# gameboyzero-split-top.net
KiCad netlist of a schematic drawn in EAGLE
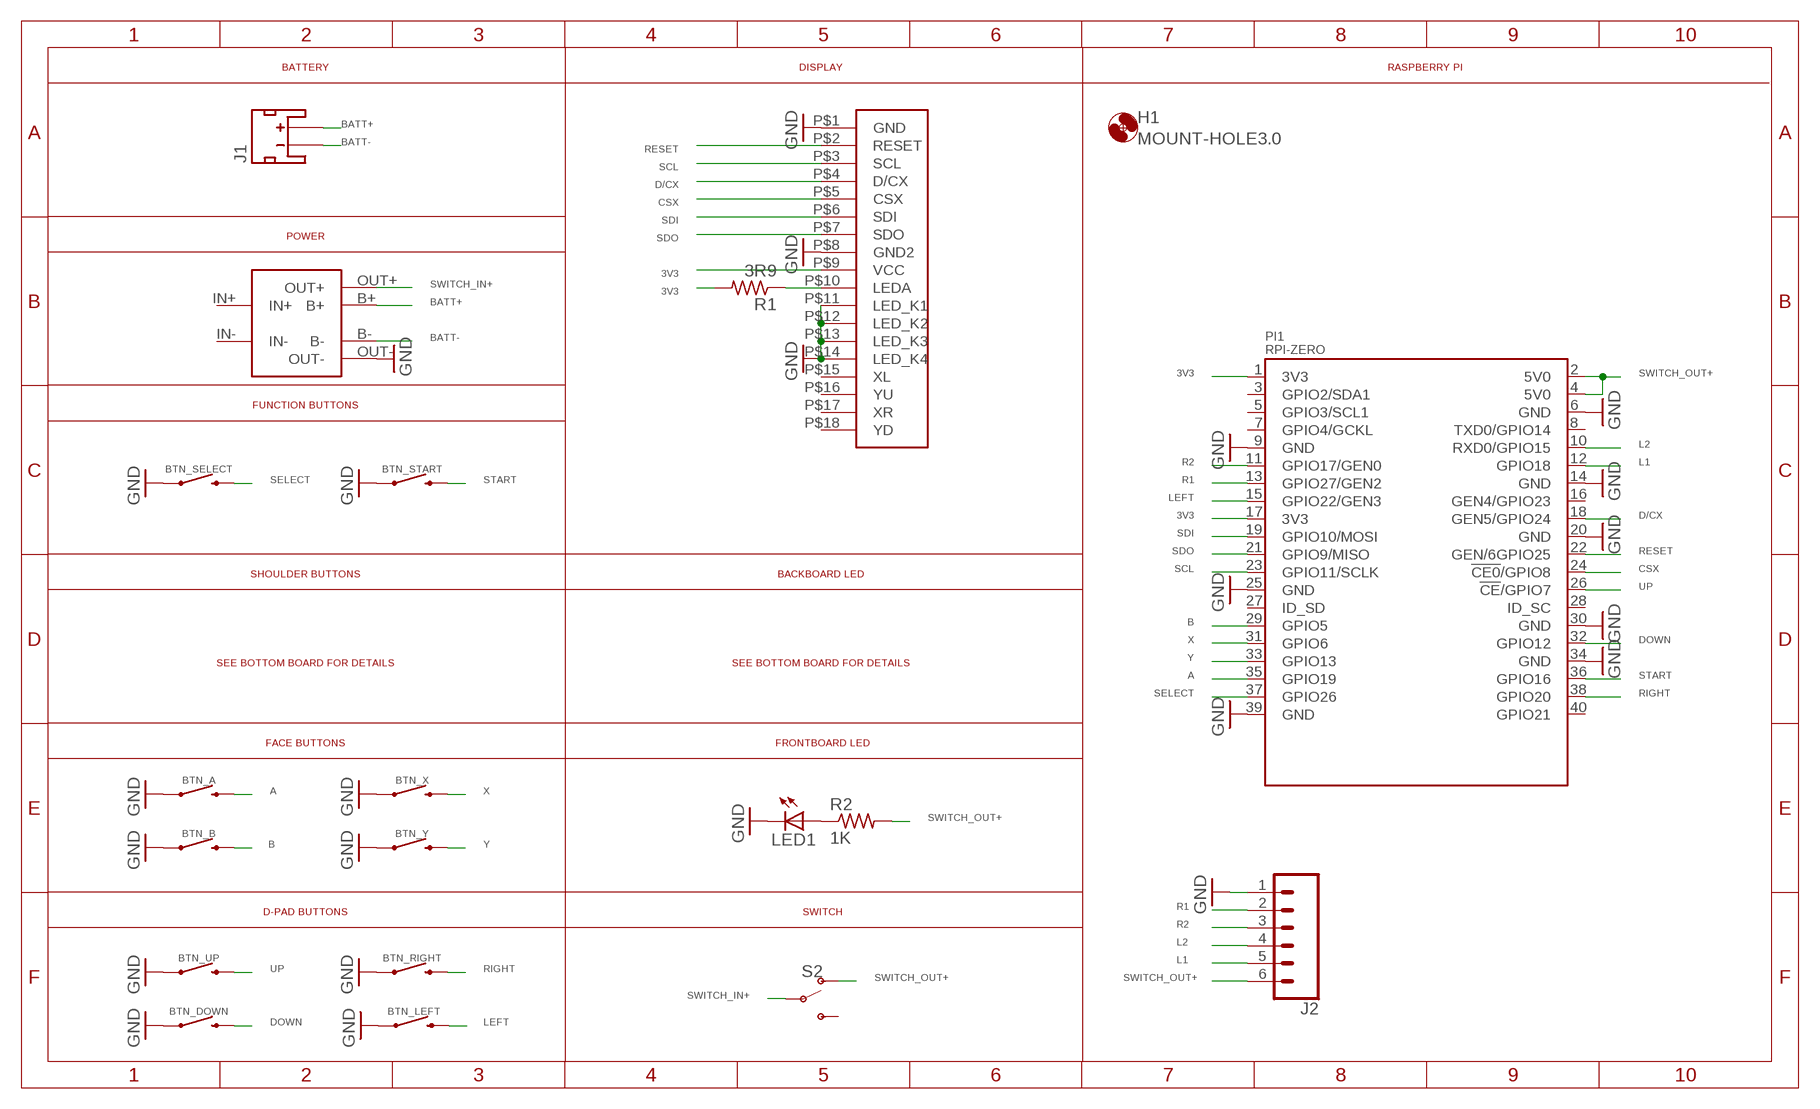
[diagram p0: schematic, sheet 1]

(export (version "E")
  (design (tool "Eeschema 10.0.6"))
  (components
    (comp (ref "BTN_A")
      (value "MOMENTARY-SWITCH-SPST-SMD-12MM")
      (footprint "eagle-import:TACTILE_SWITCH_SMD_12MM")
      (libsource (lib "eagle-import") (part "MOMENTARY-SWITCH-SPST-SMD-12MM"))
    )
    (comp (ref "BTN_B")
      (value "MOMENTARY-SWITCH-SPST-SMD-12MM")
      (footprint "eagle-import:TACTILE_SWITCH_SMD_12MM")
      (libsource (lib "eagle-import") (part "MOMENTARY-SWITCH-SPST-SMD-12MM"))
    )
    (comp (ref "BTN_DOWN")
      (value "MOMENTARY-SWITCH-SPST-SMD-6.2MM-TALL")
      (footprint "eagle-import:TACTILE_SWITCH_SMD_6.2MM_TALL")
      (libsource (lib "eagle-import") (part "MOMENTARY-SWITCH-SPST-SMD-6.2MM-TALL"))
    )
    (comp (ref "BTN_LEFT")
      (value "MOMENTARY-SWITCH-SPST-SMD-6.2MM-TALL")
      (footprint "eagle-import:TACTILE_SWITCH_SMD_6.2MM_TALL")
      (libsource (lib "eagle-import") (part "MOMENTARY-SWITCH-SPST-SMD-6.2MM-TALL"))
    )
    (comp (ref "BTN_RIGHT")
      (value "MOMENTARY-SWITCH-SPST-SMD-6.2MM-TALL")
      (footprint "eagle-import:TACTILE_SWITCH_SMD_6.2MM_TALL")
      (libsource (lib "eagle-import") (part "MOMENTARY-SWITCH-SPST-SMD-6.2MM-TALL"))
    )
    (comp (ref "BTN_SELECT")
      (value "MOMENTARY-SWITCH-SPST-SMD-6.0X3.5MM")
      (footprint "eagle-import:TACTILE_SWITCH_SMD_6.0X3.5MM")
      (libsource (lib "eagle-import") (part "MOMENTARY-SWITCH-SPST-SMD-6.0X3.5MM"))
    )
    (comp (ref "BTN_START")
      (value "MOMENTARY-SWITCH-SPST-SMD-6.0X3.5MM")
      (footprint "eagle-import:TACTILE_SWITCH_SMD_6.0X3.5MM")
      (libsource (lib "eagle-import") (part "MOMENTARY-SWITCH-SPST-SMD-6.0X3.5MM"))
    )
    (comp (ref "BTN_UP")
      (value "MOMENTARY-SWITCH-SPST-SMD-6.2MM-TALL")
      (footprint "eagle-import:TACTILE_SWITCH_SMD_6.2MM_TALL")
      (libsource (lib "eagle-import") (part "MOMENTARY-SWITCH-SPST-SMD-6.2MM-TALL"))
    )
    (comp (ref "BTN_X")
      (value "MOMENTARY-SWITCH-SPST-SMD-12MM")
      (footprint "eagle-import:TACTILE_SWITCH_SMD_12MM")
      (libsource (lib "eagle-import") (part "MOMENTARY-SWITCH-SPST-SMD-12MM"))
    )
    (comp (ref "BTN_Y")
      (value "MOMENTARY-SWITCH-SPST-SMD-12MM")
      (footprint "eagle-import:TACTILE_SWITCH_SMD_12MM")
      (libsource (lib "eagle-import") (part "MOMENTARY-SWITCH-SPST-SMD-12MM"))
    )
    (comp (ref "H1")
      (value "MOUNT-HOLE3.0")
      (footprint "eagle-import:3,0")
      (libsource (lib "eagle-import") (part "MOUNT-HOLE3.0"))
    )
    (comp (ref "J1")
      (value "JST_2MM_MALE")
      (footprint "eagle-import:JST-2-SMD")
      (libsource (lib "eagle-import") (part "JST_2MM_MALE"))
    )
    (comp (ref "J2")
      (value "CONN_06SILK_FEMALE_PTH")
      (footprint "eagle-import:1X06")
      (libsource (lib "eagle-import") (part "CONN_06SILK_FEMALE_PTH"))
    )
    (comp (ref "LED1")
      (value "LEDCHIPLED_0805")
      (footprint "eagle-import:CHIPLED_0805")
      (libsource (lib "eagle-import") (part "LEDCHIPLED_0805"))
    )
    (comp (ref "PI1")
      (value "RPI-ZERO")
      (footprint "eagle-import:RASPBERRYPI_BASTELSTUBE_V13_RASPI_BOARD_B+_FULL")
      (libsource (lib "eagle-import") (part "RPI-ZERO"))
    )
    (comp (ref "POWER1")
      (value "03962A")
      (footprint "eagle-import:03962A")
      (libsource (lib "eagle-import") (part "03962A"))
    )
    (comp (ref "R1")
      (value "3R9")
      (footprint "eagle-import:R0805")
      (libsource (lib "eagle-import") (part "R-US_R0805"))
    )
    (comp (ref "R2")
      (value "1K")
      (footprint "eagle-import:R0805")
      (libsource (lib "eagle-import") (part "R-US_R0805"))
    )
    (comp (ref "S2")
      (value "SWITCH-SPDT-SMD-RIGHT-ANGLE")
      (footprint "eagle-import:SWITCH_SPST_SMD_A")
      (libsource (lib "eagle-import") (part "SWITCH-SPDT-SMD-RIGHT-ANGLE"))
    )
    (comp (ref "SCREEN1")
      (value "GAMEBOYZEROHANDHELDDISPLAYS-2.8")
      (footprint "eagle-import:GAMEBOYZEROHANDHELDDISPLAYS-2.8")
      (libsource (lib "eagle-import") (part "GAMEBOYZEROHANDHELDDISPLAYS-2.8"))
    )
  )
  (nets
    (net (code "1") (name "/3V3") (class "Default")
      (node (ref "PI1") (pin "1") (pinfunction "3V3_1") (pintype "power_in"))
      (node (ref "PI1") (pin "17") (pinfunction "3V3_17") (pintype "power_in"))
      (node (ref "R1") (pin "2") (pinfunction "2_2") (pintype "passive"))
      (node (ref "SCREEN1") (pin "P$9") (pinfunction "VCC_P$9") (pintype "bidirectional"))
    )
    (net (code "2") (name "/A") (class "Default")
      (node (ref "BTN_A") (pin "3") (pinfunction "2_3") (pintype "passive"))
      (node (ref "PI1") (pin "35") (pinfunction "GPIO19_35") (pintype "bidirectional"))
    )
    (net (code "3") (name "/B") (class "Default")
      (node (ref "BTN_B") (pin "3") (pinfunction "2_3") (pintype "passive"))
      (node (ref "PI1") (pin "29") (pinfunction "GPIO5_29") (pintype "bidirectional"))
    )
    (net (code "4") (name "/BATT+") (class "Default")
      (node (ref "J1") (pin "2") (pinfunction "+_2") (pintype "bidirectional"))
      (node (ref "POWER1") (pin "B+") (pinfunction "B+_B+") (pintype "bidirectional"))
    )
    (net (code "5") (name "/BATT-") (class "Default")
      (node (ref "J1") (pin "1") (pinfunction "-_1") (pintype "bidirectional"))
      (node (ref "POWER1") (pin "B-") (pinfunction "B-_B-") (pintype "bidirectional"))
    )
    (net (code "6") (name "/CSX") (class "Default")
      (node (ref "PI1") (pin "24") (pinfunction "~{CE0}/GPIO8_24") (pintype "bidirectional"))
      (node (ref "SCREEN1") (pin "P$5") (pinfunction "CSX_P$5") (pintype "bidirectional"))
    )
    (net (code "7") (name "/DOWN") (class "Default")
      (node (ref "BTN_DOWN") (pin "B2") (pinfunction "2_B2") (pintype "passive"))
      (node (ref "PI1") (pin "32") (pinfunction "GPIO12_32") (pintype "bidirectional"))
    )
    (net (code "8") (name "/D{slash}CX") (class "Default")
      (node (ref "PI1") (pin "18") (pinfunction "GEN5/GPIO24_18") (pintype "bidirectional"))
      (node (ref "SCREEN1") (pin "P$4") (pinfunction "D/CX_P$4") (pintype "bidirectional"))
    )
    (net (code "9") (name "/L1") (class "Default")
      (node (ref "J2") (pin "5") (pinfunction "5_5") (pintype "passive"))
      (node (ref "PI1") (pin "12") (pinfunction "GPIO18_12") (pintype "bidirectional"))
    )
    (net (code "10") (name "/L2") (class "Default")
      (node (ref "J2") (pin "4") (pinfunction "4_4") (pintype "passive"))
      (node (ref "PI1") (pin "10") (pinfunction "RXD0/GPIO15_10") (pintype "bidirectional"))
    )
    (net (code "11") (name "/LEFT") (class "Default")
      (node (ref "BTN_LEFT") (pin "B2") (pinfunction "2_B2") (pintype "passive"))
      (node (ref "PI1") (pin "15") (pinfunction "GPIO22/GEN3_15") (pintype "bidirectional"))
    )
    (net (code "12") (name "/R1") (class "Default")
      (node (ref "J2") (pin "2") (pinfunction "2_2") (pintype "passive"))
      (node (ref "PI1") (pin "13") (pinfunction "GPIO27/GEN2_13") (pintype "bidirectional"))
    )
    (net (code "13") (name "/R2") (class "Default")
      (node (ref "J2") (pin "3") (pinfunction "3_3") (pintype "passive"))
      (node (ref "PI1") (pin "11") (pinfunction "GPIO17/GEN0_11") (pintype "bidirectional"))
    )
    (net (code "14") (name "/RESET") (class "Default")
      (node (ref "PI1") (pin "22") (pinfunction "GEN/6GPIO25_22") (pintype "bidirectional"))
      (node (ref "SCREEN1") (pin "P$2") (pinfunction "RESET_P$2") (pintype "bidirectional"))
    )
    (net (code "15") (name "/RIGHT") (class "Default")
      (node (ref "BTN_RIGHT") (pin "B2") (pinfunction "2_B2") (pintype "passive"))
      (node (ref "PI1") (pin "38") (pinfunction "GPIO20_38") (pintype "bidirectional"))
    )
    (net (code "16") (name "/SCL") (class "Default")
      (node (ref "PI1") (pin "23") (pinfunction "GPIO11/SCLK_23") (pintype "bidirectional"))
      (node (ref "SCREEN1") (pin "P$3") (pinfunction "SCL_P$3") (pintype "bidirectional"))
    )
    (net (code "17") (name "/SDI") (class "Default")
      (node (ref "PI1") (pin "19") (pinfunction "GPIO10/MOSI_19") (pintype "bidirectional"))
      (node (ref "SCREEN1") (pin "P$6") (pinfunction "SDI_P$6") (pintype "bidirectional"))
    )
    (net (code "18") (name "/SDO") (class "Default")
      (node (ref "PI1") (pin "21") (pinfunction "GPIO9/MISO_21") (pintype "bidirectional"))
      (node (ref "SCREEN1") (pin "P$7") (pinfunction "SDO_P$7") (pintype "bidirectional"))
    )
    (net (code "19") (name "/SELECT") (class "Default")
      (node (ref "BTN_SELECT") (pin "2") (pinfunction "2_2") (pintype "passive"))
      (node (ref "PI1") (pin "37") (pinfunction "GPIO26_37") (pintype "bidirectional"))
    )
    (net (code "20") (name "/START") (class "Default")
      (node (ref "BTN_START") (pin "2") (pinfunction "2_2") (pintype "passive"))
      (node (ref "PI1") (pin "36") (pinfunction "GPIO16_36") (pintype "bidirectional"))
    )
    (net (code "21") (name "/SWITCH_IN+") (class "Default")
      (node (ref "POWER1") (pin "OUT+") (pinfunction "OUT+_OUT+") (pintype "bidirectional"))
      (node (ref "S2") (pin "2") (pinfunction "P_2") (pintype "passive"))
    )
    (net (code "22") (name "/SWITCH_OUT+") (class "Default")
      (node (ref "J2") (pin "6") (pinfunction "6_6") (pintype "passive"))
      (node (ref "PI1") (pin "2") (pinfunction "5V0_2") (pintype "power_in"))
      (node (ref "PI1") (pin "4") (pinfunction "5V0_4") (pintype "power_in"))
      (node (ref "R2") (pin "2") (pinfunction "2_2") (pintype "passive"))
      (node (ref "S2") (pin "1") (pinfunction "O_1") (pintype "passive"))
    )
    (net (code "23") (name "/UP") (class "Default")
      (node (ref "BTN_UP") (pin "B2") (pinfunction "2_B2") (pintype "passive"))
      (node (ref "PI1") (pin "26") (pinfunction "~{CE}/GPIO7_26") (pintype "bidirectional"))
    )
    (net (code "24") (name "/X") (class "Default")
      (node (ref "BTN_X") (pin "3") (pinfunction "2_3") (pintype "passive"))
      (node (ref "PI1") (pin "31") (pinfunction "GPIO6_31") (pintype "bidirectional"))
    )
    (net (code "25") (name "/Y") (class "Default")
      (node (ref "BTN_Y") (pin "3") (pinfunction "2_3") (pintype "passive"))
      (node (ref "PI1") (pin "33") (pinfunction "GPIO13_33") (pintype "bidirectional"))
    )
    (net (code "26") (name "GND") (class "Default")
      (node (ref "BTN_A") (pin "1") (pinfunction "1_1") (pintype "passive"))
      (node (ref "BTN_B") (pin "1") (pinfunction "1_1") (pintype "passive"))
      (node (ref "BTN_DOWN") (pin "A2") (pinfunction "1_A2") (pintype "passive"))
      (node (ref "BTN_LEFT") (pin "A2") (pinfunction "1_A2") (pintype "passive"))
      (node (ref "BTN_RIGHT") (pin "A2") (pinfunction "1_A2") (pintype "passive"))
      (node (ref "BTN_SELECT") (pin "1") (pinfunction "1_1") (pintype "passive"))
      (node (ref "BTN_START") (pin "1") (pinfunction "1_1") (pintype "passive"))
      (node (ref "BTN_UP") (pin "A2") (pinfunction "1_A2") (pintype "passive"))
      (node (ref "BTN_X") (pin "1") (pinfunction "1_1") (pintype "passive"))
      (node (ref "BTN_Y") (pin "1") (pinfunction "1_1") (pintype "passive"))
      (node (ref "J2") (pin "1") (pinfunction "1_1") (pintype "passive"))
      (node (ref "LED1") (pin "C") (pinfunction "C_C") (pintype "passive"))
      (node (ref "PI1") (pin "14") (pinfunction "GND_14") (pintype "power_in"))
      (node (ref "PI1") (pin "20") (pinfunction "GND_20") (pintype "power_in"))
      (node (ref "PI1") (pin "25") (pinfunction "GND_25") (pintype "power_in"))
      (node (ref "PI1") (pin "30") (pinfunction "GND_30") (pintype "power_in"))
      (node (ref "PI1") (pin "34") (pinfunction "GND_34") (pintype "power_in"))
      (node (ref "PI1") (pin "39") (pinfunction "GND_39") (pintype "power_in"))
      (node (ref "PI1") (pin "6") (pinfunction "GND_6") (pintype "power_in"))
      (node (ref "PI1") (pin "9") (pinfunction "GND_9") (pintype "power_in"))
      (node (ref "POWER1") (pin "OUT-") (pinfunction "OUT-_OUT-") (pintype "bidirectional"))
      (node (ref "SCREEN1") (pin "P$1") (pinfunction "GND_P$1") (pintype "bidirectional"))
      (node (ref "SCREEN1") (pin "P$11") (pinfunction "LED_K1_P$11") (pintype "bidirectional"))
      (node (ref "SCREEN1") (pin "P$12") (pinfunction "LED_K2_P$12") (pintype "bidirectional"))
      (node (ref "SCREEN1") (pin "P$13") (pinfunction "LED_K3_P$13") (pintype "bidirectional"))
      (node (ref "SCREEN1") (pin "P$14") (pinfunction "LED_K4_P$14") (pintype "bidirectional"))
      (node (ref "SCREEN1") (pin "P$8") (pinfunction "GND2_P$8") (pintype "bidirectional"))
    )
    (net (code "27") (name "Net-(LED1-PadA)") (class "Default")
      (node (ref "LED1") (pin "A") (pinfunction "A_A") (pintype "passive"))
      (node (ref "R2") (pin "1") (pinfunction "1_1") (pintype "passive"))
    )
    (net (code "28") (name "Net-(SCREEN1-LEDA)") (class "Default")
      (node (ref "R1") (pin "1") (pinfunction "1_1") (pintype "passive"))
      (node (ref "SCREEN1") (pin "P$10") (pinfunction "LEDA_P$10") (pintype "bidirectional"))
    )
    (net (code "29") (name "unconnected-(J1-PAD1-PadNC1)") (class "Default")
      (node (ref "J1") (pin "NC1") (pinfunction "PAD1_NC1") (pintype "bidirectional"))
    )
    (net (code "30") (name "unconnected-(J1-PAD2-PadNC2)") (class "Default")
      (node (ref "J1") (pin "NC2") (pinfunction "PAD2_NC2") (pintype "bidirectional"))
    )
    (net (code "31") (name "unconnected-(PI1-GEN4{slash}GPIO23-Pad16)") (class "Default")
      (node (ref "PI1") (pin "16") (pinfunction "GEN4/GPIO23_16") (pintype "bidirectional"))
    )
    (net (code "32") (name "unconnected-(PI1-GPIO2{slash}SDA1-Pad3)") (class "Default")
      (node (ref "PI1") (pin "3") (pinfunction "GPIO2/SDA1_3") (pintype "bidirectional"))
    )
    (net (code "33") (name "unconnected-(PI1-GPIO3{slash}SCL1-Pad5)") (class "Default")
      (node (ref "PI1") (pin "5") (pinfunction "GPIO3/SCL1_5") (pintype "bidirectional"))
    )
    (net (code "34") (name "unconnected-(PI1-GPIO4{slash}GCKL-Pad7)") (class "Default")
      (node (ref "PI1") (pin "7") (pinfunction "GPIO4/GCKL_7") (pintype "bidirectional"))
    )
    (net (code "35") (name "unconnected-(PI1-GPIO21-Pad40)") (class "Default")
      (node (ref "PI1") (pin "40") (pinfunction "GPIO21_40") (pintype "bidirectional"))
    )
    (net (code "36") (name "unconnected-(PI1-ID_SC-Pad28)") (class "Default")
      (node (ref "PI1") (pin "28") (pinfunction "ID_SC_28") (pintype "bidirectional"))
    )
    (net (code "37") (name "unconnected-(PI1-ID_SD-Pad27)") (class "Default")
      (node (ref "PI1") (pin "27") (pinfunction "ID_SD_27") (pintype "bidirectional"))
    )
    (net (code "38") (name "unconnected-(PI1-TXD0{slash}GPIO14-Pad8)") (class "Default")
      (node (ref "PI1") (pin "8") (pinfunction "TXD0/GPIO14_8") (pintype "bidirectional"))
    )
    (net (code "39") (name "unconnected-(POWER1-PadIN+)") (class "Default")
      (node (ref "POWER1") (pin "IN+") (pinfunction "IN+_IN+") (pintype "bidirectional"))
    )
    (net (code "40") (name "unconnected-(POWER1-PadIN-)") (class "Default")
      (node (ref "POWER1") (pin "IN-") (pinfunction "IN-_IN-") (pintype "bidirectional"))
    )
    (net (code "41") (name "unconnected-(S2-S-Pad3)") (class "Default")
      (node (ref "S2") (pin "3") (pinfunction "S_3") (pintype "passive"))
    )
    (net (code "42") (name "unconnected-(SCREEN1-XL-PadP$15)") (class "Default")
      (node (ref "SCREEN1") (pin "P$15") (pinfunction "XL_P$15") (pintype "bidirectional"))
    )
    (net (code "43") (name "unconnected-(SCREEN1-XR-PadP$17)") (class "Default")
      (node (ref "SCREEN1") (pin "P$17") (pinfunction "XR_P$17") (pintype "bidirectional"))
    )
    (net (code "44") (name "unconnected-(SCREEN1-YD-PadP$18)") (class "Default")
      (node (ref "SCREEN1") (pin "P$18") (pinfunction "YD_P$18") (pintype "bidirectional"))
    )
    (net (code "45") (name "unconnected-(SCREEN1-YU-PadP$16)") (class "Default")
      (node (ref "SCREEN1") (pin "P$16") (pinfunction "YU_P$16") (pintype "bidirectional"))
    )
  )
)
